# not.net
KiCad netlist of a schematic drawn in EAGLE
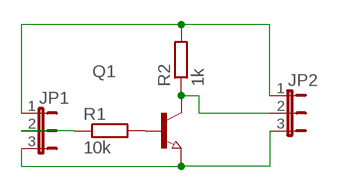
[diagram p0: schematic, sheet 1]

(export (version "E")
  (design (tool "Eeschema 10.0.6"))
  (components
    (comp (ref "JP1")
      (value "JP2W")
      (footprint "eagle-import:JP2W")
      (libsource (lib "eagle-import") (part "JP2W"))
    )
    (comp (ref "JP2")
      (value "JP2W")
      (footprint "eagle-import:JP2W")
      (libsource (lib "eagle-import") (part "JP2W"))
    )
    (comp (ref "Q1")
      (value "NPN-TRANSISTOR_SOT23")
      (footprint "eagle-import:SOT23")
      (libsource (lib "eagle-import") (part "NPN-TRANSISTOR_SOT23"))
    )
    (comp (ref "R1")
      (value "10k")
      (footprint "eagle-import:R1206")
      (libsource (lib "eagle-import") (part "R-EU_R1206"))
    )
    (comp (ref "R2")
      (value "1k")
      (footprint "eagle-import:R1206")
      (libsource (lib "eagle-import") (part "R-EU_R1206"))
    )
  )
  (nets
    (net (code "1") (name "Net-(JP1-Pad1)") (class "Default")
      (node (ref "JP1") (pin "1") (pinfunction "1_1") (pintype "passive"))
      (node (ref "JP2") (pin "1") (pinfunction "1_1") (pintype "passive"))
      (node (ref "R2") (pin "2") (pinfunction "2_2") (pintype "passive"))
    )
    (net (code "2") (name "Net-(JP1-Pad2)") (class "Default")
      (node (ref "JP1") (pin "2") (pinfunction "2_2") (pintype "passive"))
      (node (ref "R1") (pin "1") (pinfunction "1_1") (pintype "passive"))
    )
    (net (code "3") (name "Net-(Q1-B)") (class "Default")
      (node (ref "Q1") (pin "1") (pinfunction "B_1") (pintype "passive"))
      (node (ref "R1") (pin "2") (pinfunction "2_2") (pintype "passive"))
    )
    (net (code "4") (name "Net-(Q1-C)") (class "Default")
      (node (ref "JP2") (pin "2") (pinfunction "2_2") (pintype "passive"))
      (node (ref "Q1") (pin "3") (pinfunction "C_3") (pintype "passive"))
      (node (ref "R2") (pin "1") (pinfunction "1_1") (pintype "passive"))
    )
    (net (code "5") (name "Net-(Q1-E)") (class "Default")
      (node (ref "JP1") (pin "3") (pinfunction "3_3") (pintype "passive"))
      (node (ref "JP2") (pin "3") (pinfunction "3_3") (pintype "passive"))
      (node (ref "Q1") (pin "2") (pinfunction "E_2") (pintype "passive"))
    )
  )
)
